# SAM_E54_Xplained_Pro_current_measurement.net
KiCad netlist of a schematic drawn in Altium Designer
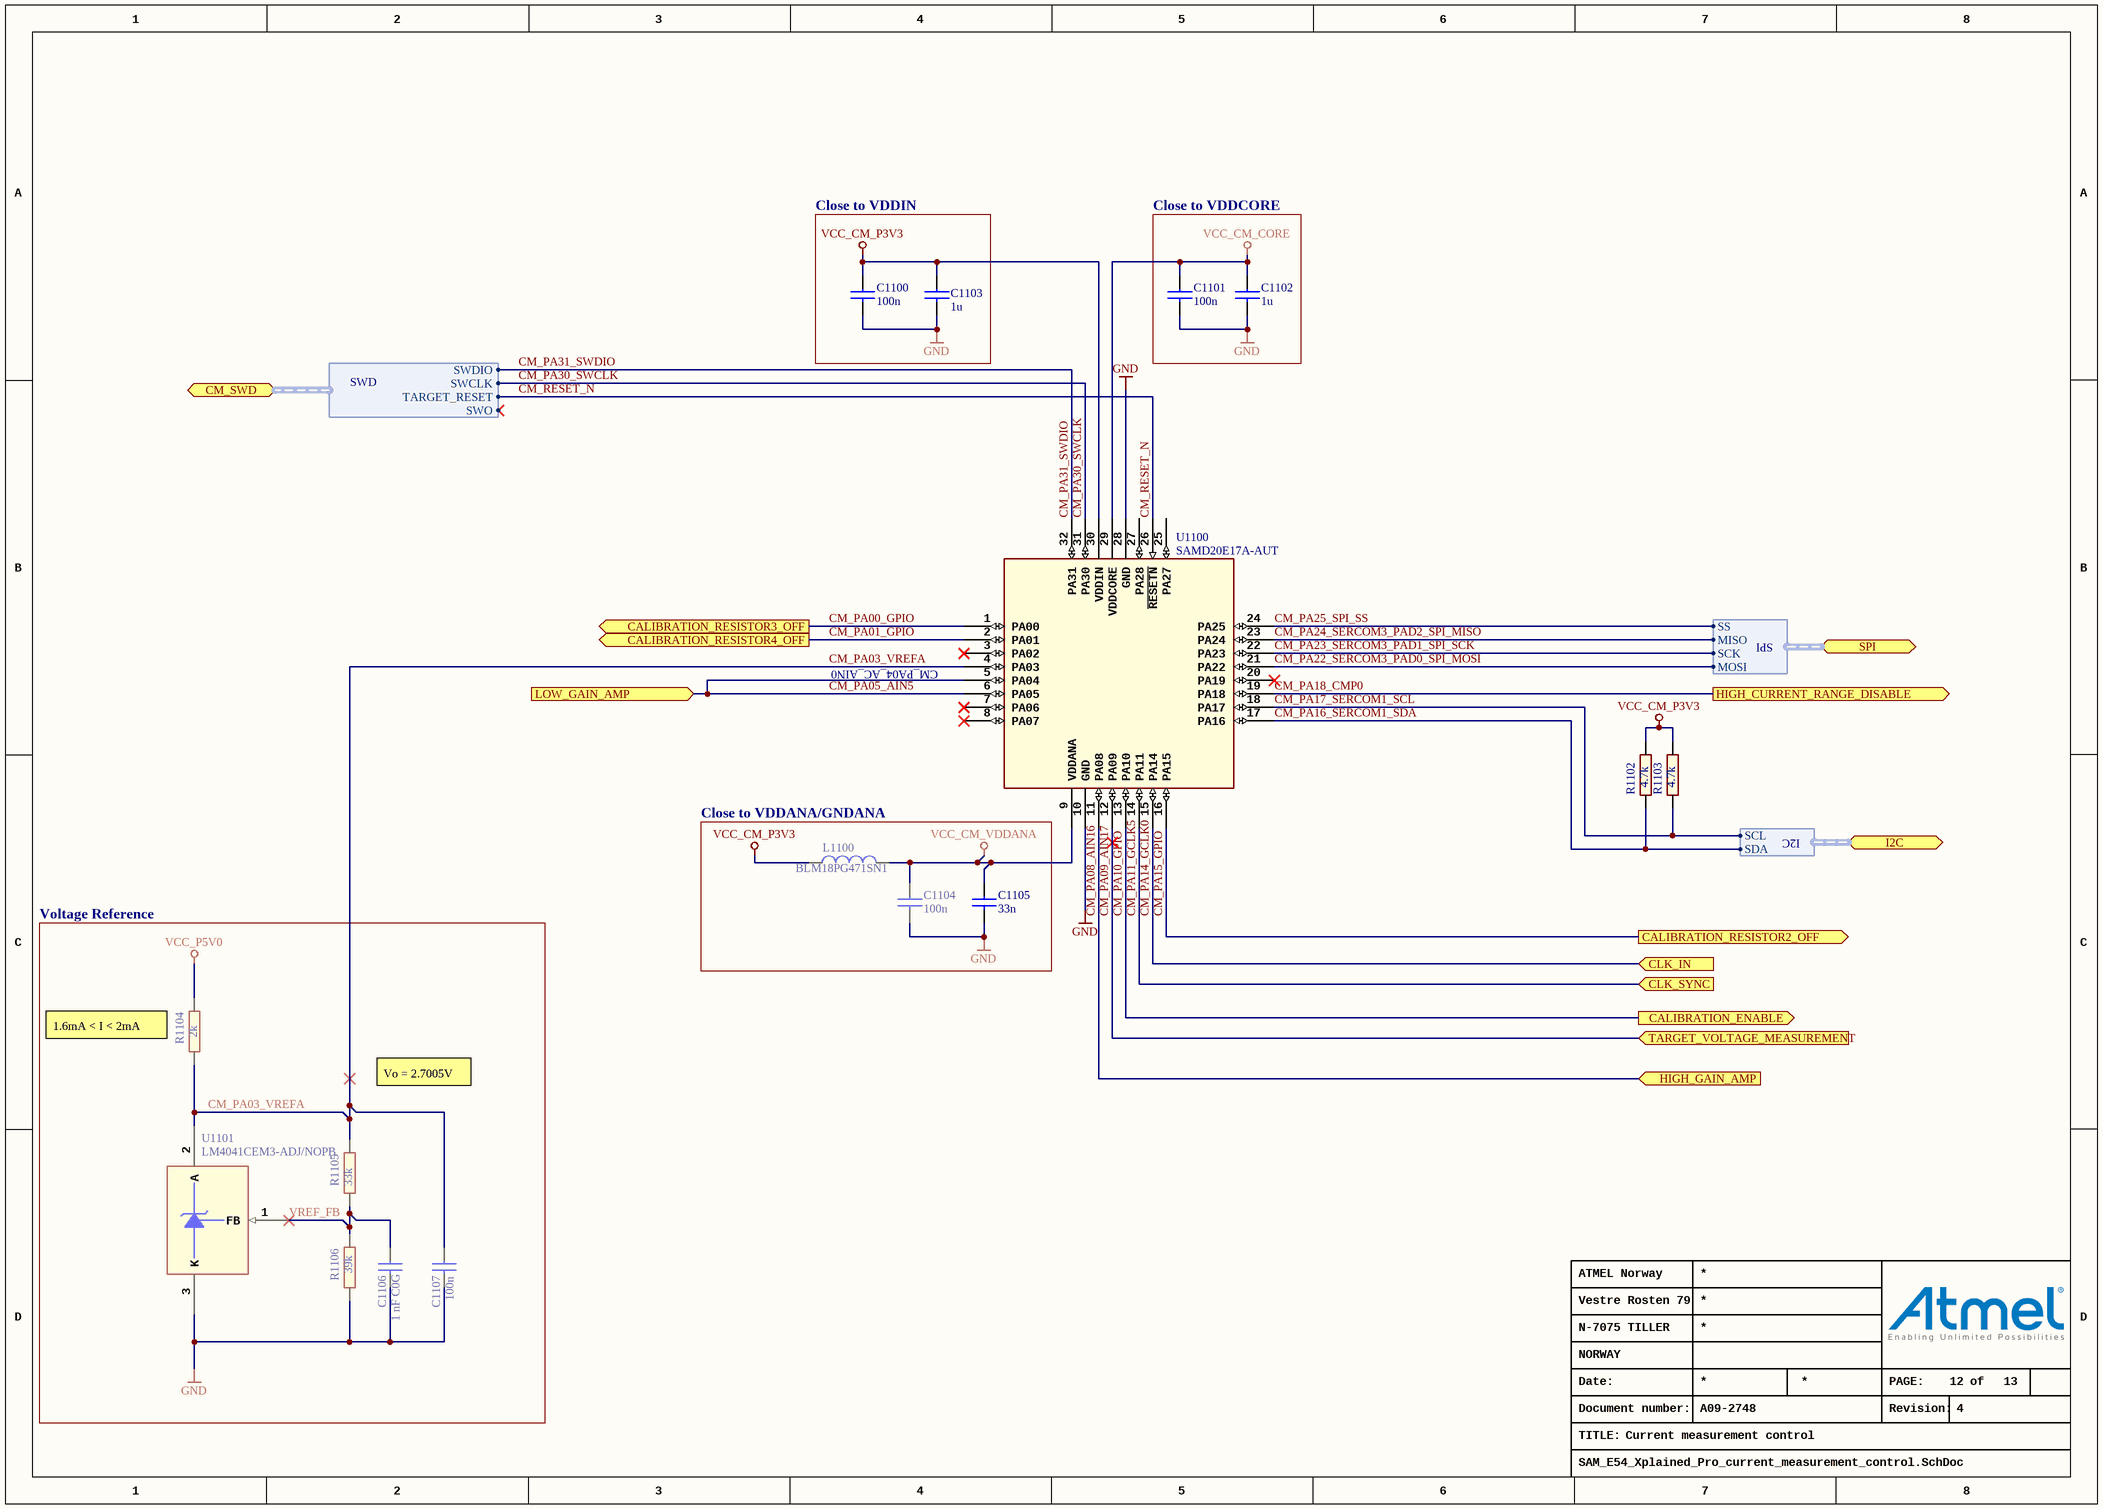
[diagram p0: SAM_E54_Xplained_Pro_current_measurement_control.SchDoc]

(export (version "E")
  (design (tool "Eeschema 10.0.6"))
  (components
    (comp (ref "C1100")
      (value "100n")
      (footprint "AP1-00053")
      (description "Ceramic capacitor, SMD 0402, X7R, 16V, +/-10%")
      (fields (field (name "TOLERANCE") "16V, +/-10%") (field (name "MANUFACTURER") "Kemet"))
      (libsource (lib "AltiumDbLib") (part "CAP-NONPOL"))
    )
    (comp (ref "C1101")
      (value "100n")
      (footprint "AP1-00053")
      (description "Ceramic capacitor, SMD 0402, X7R, 16V, +/-10%")
      (fields (field (name "TOLERANCE") "16V, +/-10%") (field (name "MANUFACTURER") "Kemet"))
      (libsource (lib "AltiumDbLib") (part "CAP-NONPOL"))
    )
    (comp (ref "C1102")
      (value "1u")
      (footprint "AP1-00053")
      (description "Ceramic capacitor, SMD 0402, X5R, 6.3V, +/-10% (de26942)")
      (fields (field (name "TOLERANCE") "+/-10%") (field (name "MANUFACTURER") "Kemet"))
      (libsource (lib "AltiumDbLib") (part "CAP-NONPOL"))
    )
    (comp (ref "C1103")
      (value "1u")
      (footprint "AP1-00053")
      (description "Ceramic capacitor, SMD 0402, X5R, 6.3V, +/-10% (de26942)")
      (fields (field (name "TOLERANCE") "+/-10%") (field (name "MANUFACTURER") "Kemet"))
      (libsource (lib "AltiumDbLib") (part "CAP-NONPOL"))
    )
    (comp (ref "C1104")
      (value "100n")
      (footprint "AP1-00053")
      (description "Ceramic capacitor, SMD 0402, X7R, 16V, +/-10%")
      (fields (field (name "TOLERANCE") "16V, +/-10%") (field (name "MANUFACTURER") "Kemet"))
      (libsource (lib "AltiumDbLib") (part "CAP-NONPOL"))
    )
    (comp (ref "C1105")
      (value "33n")
      (footprint "AP1-00053")
      (description "Ceramic capacitor, SMD 0402, X7R, 25V, ±10%")
      (fields (field (name "TOLERANCE") "±10%(K)") (field (name "MANUFACTURER") "Murata"))
      (libsource (lib "AltiumDbLib") (part "CAP-NONPOL"))
    )
    (comp (ref "C1106")
      (value "1 nF C0G")
      (footprint "AP1-00053")
      (description "Ceramic capacitor, SMD 0402, C0G, 50V, +/-5%")
      (fields (field (name "TOLERANCE") "5%") (field (name "MANUFACTURER") "Murata"))
      (libsource (lib "AltiumDbLib") (part "CAP-NONPOL"))
    )
    (comp (ref "C1107")
      (value "100n")
      (footprint "AP1-00053")
      (description "Ceramic capacitor, SMD 0402, X7R, 16V, +/-10%")
      (fields (field (name "TOLERANCE") "16V, +/-10%") (field (name "MANUFACTURER") "Kemet"))
      (libsource (lib "AltiumDbLib") (part "CAP-NONPOL"))
    )
    (comp (ref "L1100")
      (value "BLM18PG471SN1")
      (footprint "AP3-00005")
      (description "SMD RF inductor 0603. Z=470Ohm (@100MHz), Max R(dc)=0.65Ohm, Max current=1A")
      (fields (field (name "MANUFACTURER") "Murata"))
      (libsource (lib "AltiumDbLib") (part "INDUCTOR"))
    )
    (comp (ref "R1102")
      (value "4.7k")
      (footprint "AP2-00011")
      (description "Thick film resistor, SMD 0402, 1/16W, 1%")
      (fields (field (name "TOLERANCE") "1 %") (field (name "MANUFACTURER") "PHYCOMP"))
      (libsource (lib "AltiumDbLib") (part "R2"))
    )
    (comp (ref "R1103")
      (value "4.7k")
      (footprint "AP2-00011")
      (description "Thick film resistor, SMD 0402, 1/16W, 1%")
      (fields (field (name "TOLERANCE") "1 %") (field (name "MANUFACTURER") "PHYCOMP"))
      (libsource (lib "AltiumDbLib") (part "R2"))
    )
    (comp (ref "R1104")
      (value "2k")
      (footprint "AP2-00011")
      (description "Thick film resistor, SMD 0402, 1/16W, 1%")
      (fields (field (name "TOLERANCE") "1 %"))
      (libsource (lib "") (part "R2_1"))
    )
    (comp (ref "R1105")
      (value "33k")
      (footprint "AP2-00011")
      (description "Thick film resistor, SMD 0402, 1/16W, 1%")
      (fields (field (name "TOLERANCE") "1 %") (field (name "MANUFACTURER") "ASJ"))
      (libsource (lib "") (part "R2_1"))
    )
    (comp (ref "R1106")
      (value "39k")
      (footprint "AP2-00011")
      (description "Thick film resistor, SMD 0402, 1/16W, 1%")
      (fields (field (name "TOLERANCE") "1 %") (field (name "MANUFACTURER") "ASJ"))
      (libsource (lib "") (part "R2_1"))
    )
    (comp (ref "U1100")
      (value "SAMD20E17A-AUT")
      (footprint "AP6-00061")
      (description "Atmel 32bit RISC MCU 32 pin")
      (fields (field (name "MANUFACTURER") "ATMEL") (field (name "MPN") "ATSAMD20E17A-AUT"))
      (libsource (lib "AltiumDbLib") (part "SAMD20E"))
    )
    (comp (ref "U1101")
      (value "LM4041CEM3-ADJ/NOPB")
      (footprint "AP5-00002")
      (description "Adjustable shunt voltage regulator, 1.24 to 10V out")
      (fields (field (name "MANUFACTURER") "Texas Instruments"))
      (libsource (lib "AltiumDbLib") (part "LM4041-ADJ"))
    )
  )
  (nets
    (net (code "4") (name "/CM_PA00_GPIO") (class "Default")
      (node (ref "U1100") (pin "1") (pinfunction "PA00_1") (pintype "bidirectional"))
    )
    (net (code "5") (name "/CM_PA01_GPIO") (class "Default")
      (node (ref "U1100") (pin "2") (pinfunction "PA01_2") (pintype "bidirectional"))
    )
    (net (code "6") (name "/CM_PA03_VREFA") (class "Default")
      (node (ref "C1107") (pin "1") (pinfunction "1_1") (pintype "passive"))
      (node (ref "R1104") (pin "1") (pinfunction "1_1") (pintype "passive"))
      (node (ref "R1105") (pin "2") (pinfunction "2_2") (pintype "passive"))
      (node (ref "U1100") (pin "4") (pinfunction "PA03_4") (pintype "bidirectional"))
      (node (ref "U1101") (pin "2") (pinfunction "A_2") (pintype "power_in"))
    )
    (net (code "7") (name "/CM_PA05_AIN5") (class "Default")
      (node (ref "U1100") (pin "5") (pinfunction "PA04_5") (pintype "bidirectional"))
      (node (ref "U1100") (pin "6") (pinfunction "PA05_6") (pintype "bidirectional"))
    )
    (net (code "8") (name "/CM_PA08_AIN16") (class "Default")
      (node (ref "U1100") (pin "11") (pinfunction "PA08_11") (pintype "bidirectional"))
    )
    (net (code "9") (name "/CM_PA09_AIN17") (class "Default")
      (node (ref "U1100") (pin "12") (pinfunction "PA09_12") (pintype "bidirectional"))
    )
    (net (code "10") (name "/CM_PA10_GPIO") (class "Default")
      (node (ref "U1100") (pin "13") (pinfunction "PA10_13") (pintype "bidirectional"))
    )
    (net (code "11") (name "/CM_PA11_GCLK5") (class "Default")
      (node (ref "U1100") (pin "14") (pinfunction "PA11_14") (pintype "bidirectional"))
    )
    (net (code "12") (name "/CM_PA14_GCLK0") (class "Default")
      (node (ref "U1100") (pin "15") (pinfunction "PA14_15") (pintype "bidirectional"))
    )
    (net (code "13") (name "/CM_PA15_GPIO") (class "Default")
      (node (ref "U1100") (pin "16") (pinfunction "PA15_16") (pintype "bidirectional"))
    )
    (net (code "14") (name "/CM_PA16_SERCOM1_SDA") (class "Default")
      (node (ref "R1102") (pin "1") (pinfunction "1_1") (pintype "passive"))
      (node (ref "U1100") (pin "17") (pinfunction "PA16_17") (pintype "bidirectional"))
    )
    (net (code "15") (name "/CM_PA17_SERCOM1_SCL") (class "Default")
      (node (ref "R1103") (pin "1") (pinfunction "1_1") (pintype "passive"))
      (node (ref "U1100") (pin "18") (pinfunction "PA17_18") (pintype "bidirectional"))
    )
    (net (code "16") (name "/CM_PA18_CMP0") (class "Default")
      (node (ref "U1100") (pin "19") (pinfunction "PA18_19") (pintype "bidirectional"))
    )
    (net (code "17") (name "/CM_PA22_SERCOM3_PAD0_SPI_MOSI") (class "Default")
      (node (ref "U1100") (pin "21") (pinfunction "PA22_21") (pintype "bidirectional"))
    )
    (net (code "18") (name "/CM_PA23_SERCOM3_PAD1_SPI_SCK") (class "Default")
      (node (ref "U1100") (pin "22") (pinfunction "PA23_22") (pintype "bidirectional"))
    )
    (net (code "19") (name "/CM_PA24_SERCOM3_PAD2_SPI_MISO") (class "Default")
      (node (ref "U1100") (pin "23") (pinfunction "PA24_23") (pintype "bidirectional"))
    )
    (net (code "20") (name "/CM_PA25_SPI_SS") (class "Default")
      (node (ref "U1100") (pin "24") (pinfunction "PA25_24") (pintype "bidirectional"))
    )
    (net (code "21") (name "/CM_PA30_SWCLK") (class "Default")
      (node (ref "U1100") (pin "31") (pinfunction "PA30_31") (pintype "bidirectional"))
    )
    (net (code "22") (name "/CM_PA31_SWDIO") (class "Default")
      (node (ref "U1100") (pin "32") (pinfunction "PA31_32") (pintype "bidirectional"))
    )
    (net (code "23") (name "/CM_RESET_N") (class "Default")
      (node (ref "U1100") (pin "26") (pinfunction "~{RESETN}_26") (pintype "input"))
    )
    (net (code "24") (name "/VREF_FB") (class "Default")
      (node (ref "C1106") (pin "1") (pinfunction "1_1") (pintype "passive"))
      (node (ref "R1105") (pin "1") (pinfunction "1_1") (pintype "passive"))
      (node (ref "R1106") (pin "2") (pinfunction "2_2") (pintype "passive"))
      (node (ref "U1101") (pin "1") (pinfunction "FB_1") (pintype "input"))
    )
    (net (code "28") (name "GND") (class "Default")
      (node (ref "C1100") (pin "2") (pinfunction "2_2") (pintype "passive"))
      (node (ref "C1101") (pin "2") (pinfunction "2_2") (pintype "passive"))
      (node (ref "C1102") (pin "2") (pinfunction "2_2") (pintype "passive"))
      (node (ref "C1103") (pin "2") (pinfunction "2_2") (pintype "passive"))
      (node (ref "C1104") (pin "2") (pinfunction "2_2") (pintype "passive"))
      (node (ref "C1105") (pin "2") (pinfunction "2_2") (pintype "passive"))
      (node (ref "C1106") (pin "2") (pinfunction "2_2") (pintype "passive"))
      (node (ref "C1107") (pin "2") (pinfunction "2_2") (pintype "passive"))
      (node (ref "R1106") (pin "1") (pinfunction "1_1") (pintype "passive"))
      (node (ref "U1100") (pin "10") (pinfunction "GND_10") (pintype "power_in"))
      (node (ref "U1100") (pin "28") (pinfunction "GND_28") (pintype "power_in"))
      (node (ref "U1101") (pin "3") (pinfunction "K_3") (pintype "power_in"))
    )
    (net (code "29") (name "VCC_CM_CORE") (class "Default")
      (node (ref "C1101") (pin "1") (pinfunction "1_1") (pintype "passive"))
      (node (ref "C1102") (pin "1") (pinfunction "1_1") (pintype "passive"))
      (node (ref "U1100") (pin "29") (pinfunction "VDDCORE_29") (pintype "power_in"))
    )
    (net (code "30") (name "VCC_CM_P3V3") (class "Default")
      (node (ref "C1100") (pin "1") (pinfunction "1_1") (pintype "passive"))
      (node (ref "C1103") (pin "1") (pinfunction "1_1") (pintype "passive"))
      (node (ref "L1100") (pin "1") (pinfunction "1_1") (pintype "passive"))
      (node (ref "R1102") (pin "2") (pinfunction "2_2") (pintype "passive"))
      (node (ref "R1103") (pin "2") (pinfunction "2_2") (pintype "passive"))
      (node (ref "U1100") (pin "30") (pinfunction "VDDIN_30") (pintype "power_in"))
    )
    (net (code "31") (name "VCC_CM_VDDANA") (class "Default")
      (node (ref "C1104") (pin "1") (pinfunction "1_1") (pintype "passive"))
      (node (ref "C1105") (pin "1") (pinfunction "1_1") (pintype "passive"))
      (node (ref "L1100") (pin "2") (pinfunction "2_2") (pintype "passive"))
      (node (ref "U1100") (pin "9") (pinfunction "VDDANA_9") (pintype "power_in"))
    )
    (net (code "32") (name "VCC_P5V0") (class "Default")
      (node (ref "R1104") (pin "2") (pinfunction "2_2") (pintype "passive"))
    )
    (net (code "33") (name "unconnected-(U1100-PA02-Pad3)") (class "Default")
      (node (ref "U1100") (pin "3") (pinfunction "PA02_3") (pintype "bidirectional+no_connect"))
    )
    (net (code "34") (name "unconnected-(U1100-PA06-Pad7)") (class "Default")
      (node (ref "U1100") (pin "7") (pinfunction "PA06_7") (pintype "bidirectional+no_connect"))
    )
    (net (code "35") (name "unconnected-(U1100-PA07-Pad8)") (class "Default")
      (node (ref "U1100") (pin "8") (pinfunction "PA07_8") (pintype "bidirectional+no_connect"))
    )
    (net (code "36") (name "unconnected-(U1100-PA19-Pad20)") (class "Default")
      (node (ref "U1100") (pin "20") (pinfunction "PA19_20") (pintype "bidirectional+no_connect"))
    )
    (net (code "37") (name "unconnected-(U1100-PA27-Pad25)") (class "Default")
      (node (ref "U1100") (pin "25") (pinfunction "PA27_25") (pintype "bidirectional"))
    )
    (net (code "38") (name "unconnected-(U1100-PA28-Pad27)") (class "Default")
      (node (ref "U1100") (pin "27") (pinfunction "PA28_27") (pintype "bidirectional"))
    )
  )
)
